# SWEEP.net
KiCad netlist of a schematic drawn in Altium Designer
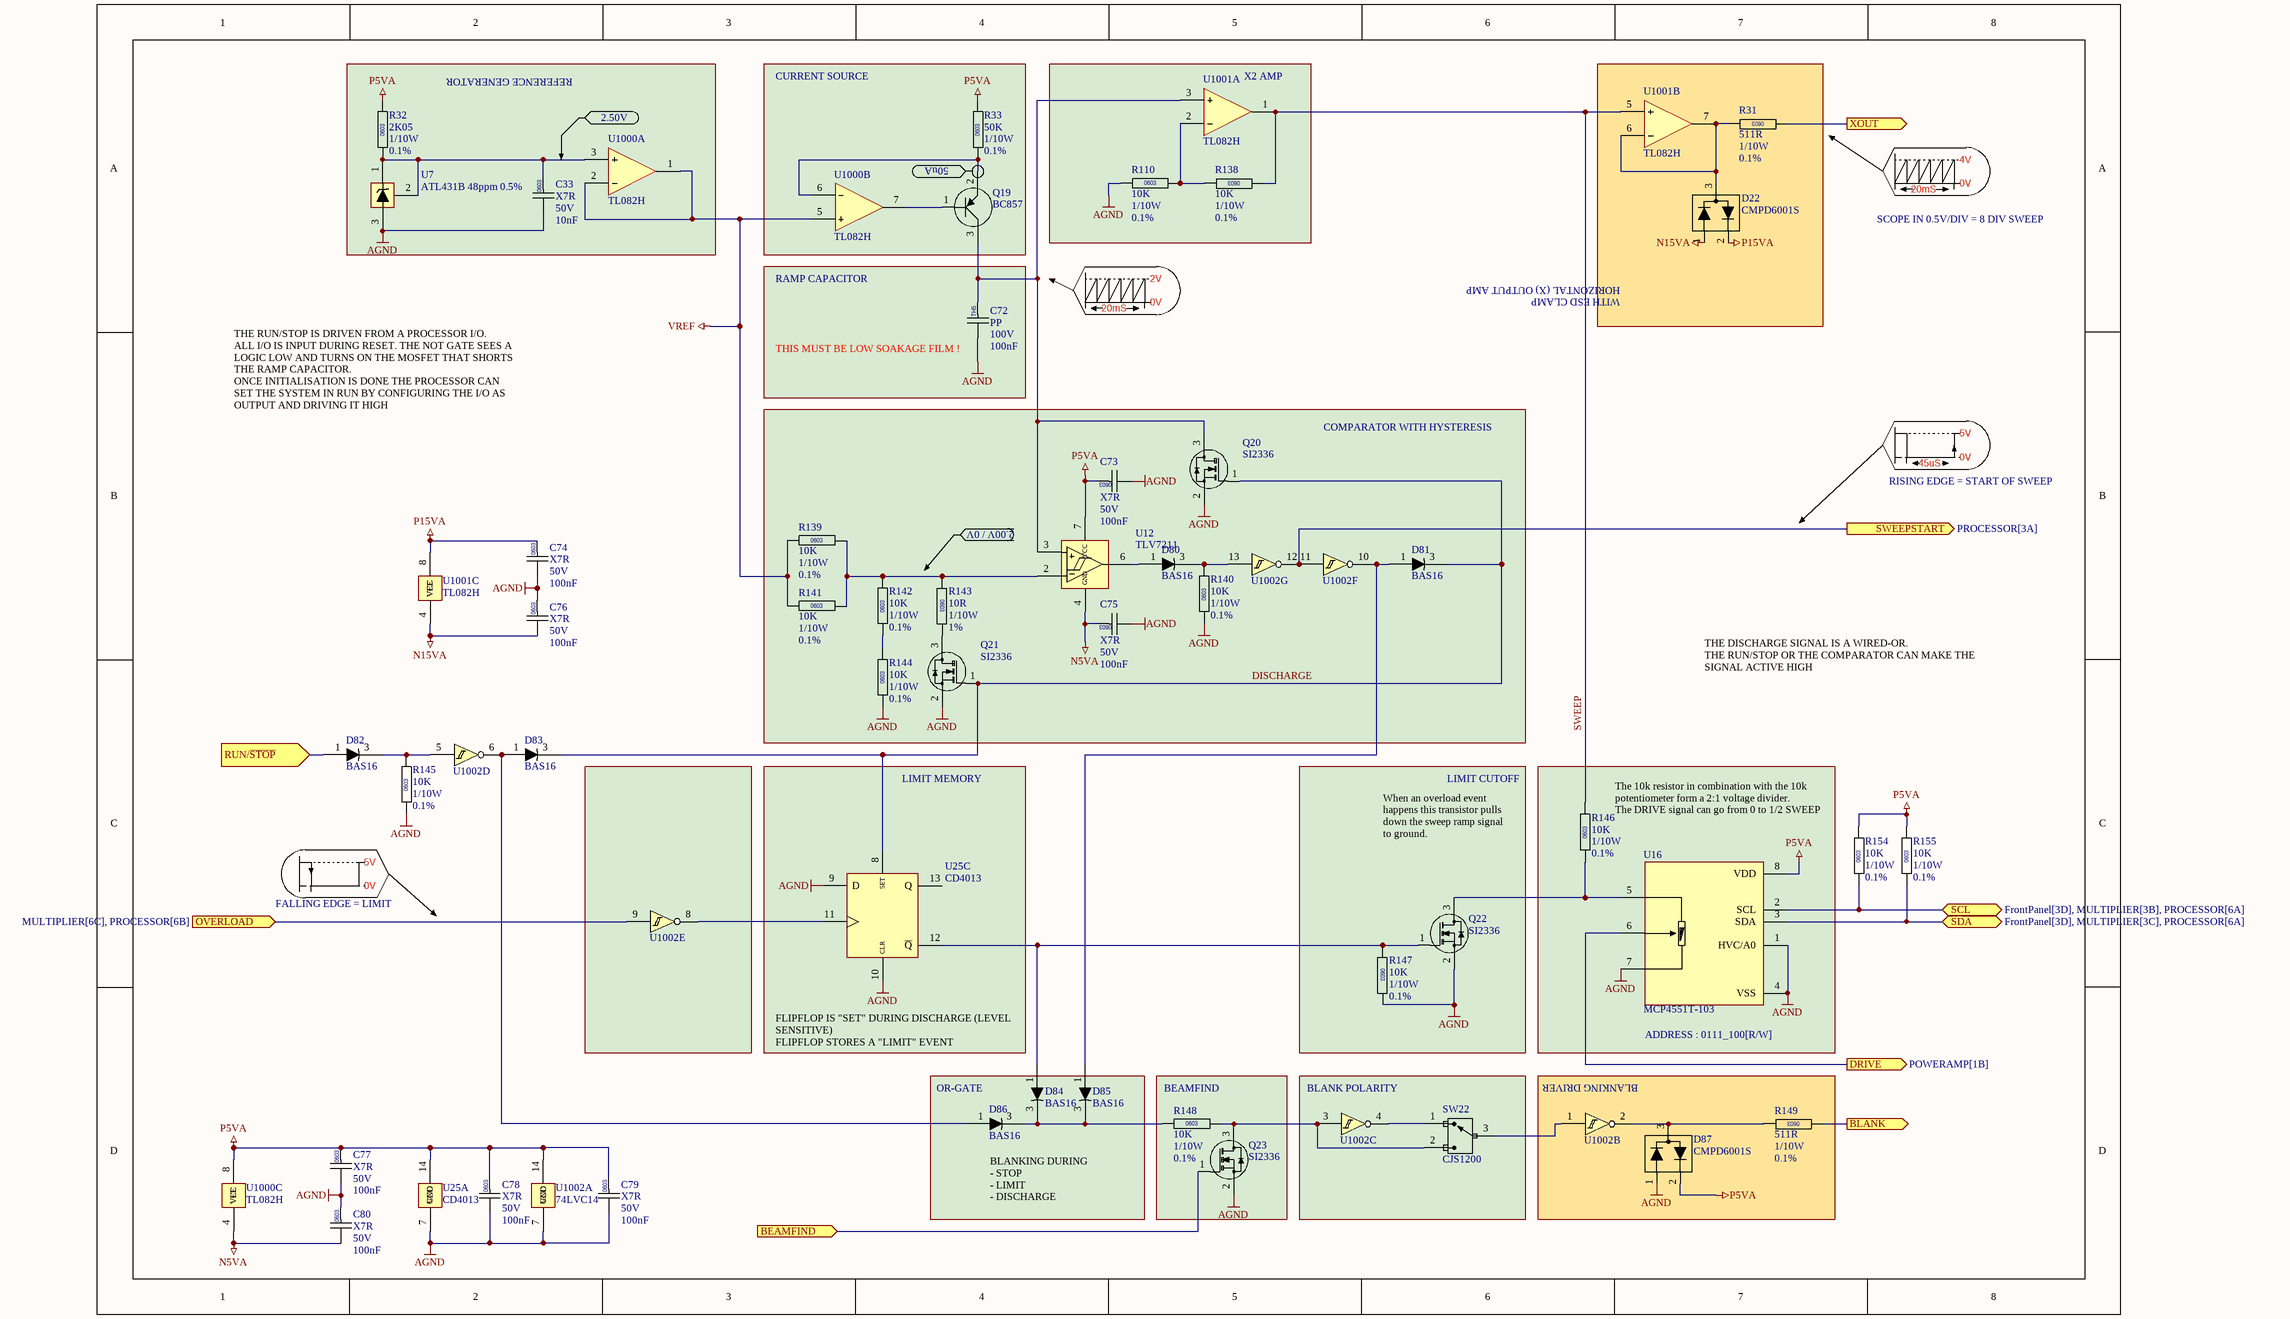
[diagram p0: SWEEP.SchDoc]

(export (version "E")
  (design (tool "Eeschema 10.0.6"))
  (components
    (comp (ref "C33")
      (value "CAP0603")
      (footprint "CAPC0603")
      (description "CAPACITOR,CERAMIC,10nF,50V,X7R,0603")
      (fields
        (field (name "DIELECTRIC") "X7R")
        (field (name "VOLTAGE") "50V")
        (field (name "CAPACITANCE") "10nF")
      )
      (libsource (lib "CAPACITORS") (part "CAPC-0603-10nF-50V-X7R"))
    )
    (comp (ref "C72")
      (value "CAPF")
      (footprint "CAPF50P720X720")
      (description "CAPACITOR,POLYPROP,100nF,100V")
      (fields
        (field (name "DIELECTRIC") "PP")
        (field (name "VOLTAGE") "100V")
        (field (name "CAPACITANCE") "100nF")
      )
      (libsource (lib "CAPACITORS") (part "CAPF-100nF-100V"))
    )
    (comp (ref "C73")
      (value "CAP0603")
      (footprint "CAPC0603")
      (description "CAPACITOR,CERAMIC,100nF,50V,X7R,0603")
      (fields
        (field (name "DIELECTRIC") "X7R")
        (field (name "VOLTAGE") "50V")
        (field (name "CAPACITANCE") "100nF")
      )
      (libsource (lib "CAPACITORS") (part "CAPC-0603-100nF-50V-X7R"))
    )
    (comp (ref "C74")
      (value "CAP0603")
      (footprint "CAPC0603")
      (description "CAPACITOR,CERAMIC,100nF,50V,X7R,0603")
      (fields
        (field (name "DIELECTRIC") "X7R")
        (field (name "VOLTAGE") "50V")
        (field (name "CAPACITANCE") "100nF")
      )
      (libsource (lib "CAPACITORS") (part "CAPC-0603-100nF-50V-X7R"))
    )
    (comp (ref "C75")
      (value "CAP0603")
      (footprint "CAPC0603")
      (description "CAPACITOR,CERAMIC,100nF,50V,X7R,0603")
      (fields
        (field (name "DIELECTRIC") "X7R")
        (field (name "VOLTAGE") "50V")
        (field (name "CAPACITANCE") "100nF")
      )
      (libsource (lib "CAPACITORS") (part "CAPC-0603-100nF-50V-X7R"))
    )
    (comp (ref "C76")
      (value "CAP0603")
      (footprint "CAPC0603")
      (description "CAPACITOR,CERAMIC,100nF,50V,X7R,0603")
      (fields
        (field (name "DIELECTRIC") "X7R")
        (field (name "VOLTAGE") "50V")
        (field (name "CAPACITANCE") "100nF")
      )
      (libsource (lib "CAPACITORS") (part "CAPC-0603-100nF-50V-X7R"))
    )
    (comp (ref "C77")
      (value "CAP0603")
      (footprint "CAPC0603")
      (description "CAPACITOR,CERAMIC,100nF,50V,X7R,0603")
      (fields
        (field (name "DIELECTRIC") "X7R")
        (field (name "VOLTAGE") "50V")
        (field (name "CAPACITANCE") "100nF")
      )
      (libsource (lib "CAPACITORS") (part "CAPC-0603-100nF-50V-X7R"))
    )
    (comp (ref "C78")
      (value "CAP0603")
      (footprint "CAPC0603")
      (description "CAPACITOR,CERAMIC,100nF,50V,X7R,0603")
      (fields
        (field (name "DIELECTRIC") "X7R")
        (field (name "VOLTAGE") "50V")
        (field (name "CAPACITANCE") "100nF")
      )
      (libsource (lib "CAPACITORS") (part "CAPC-0603-100nF-50V-X7R"))
    )
    (comp (ref "C79")
      (value "CAP0603")
      (footprint "CAPC0603")
      (description "CAPACITOR,CERAMIC,100nF,50V,X7R,0603")
      (fields
        (field (name "DIELECTRIC") "X7R")
        (field (name "VOLTAGE") "50V")
        (field (name "CAPACITANCE") "100nF")
      )
      (libsource (lib "CAPACITORS") (part "CAPC-0603-100nF-50V-X7R"))
    )
    (comp (ref "C80")
      (value "CAP0603")
      (footprint "CAPC0603")
      (description "CAPACITOR,CERAMIC,100nF,50V,X7R,0603")
      (fields
        (field (name "DIELECTRIC") "X7R")
        (field (name "VOLTAGE") "50V")
        (field (name "CAPACITANCE") "100nF")
      )
      (libsource (lib "CAPACITORS") (part "CAPC-0603-100nF-50V-X7R"))
    )
    (comp (ref "D22")
      (value "CMPD6001S")
      (footprint "SOT23")
      (description "DIODE,75V,250mA,SOT23,500pA ULTRA LOW LEAKAGE")
      (libsource (lib "DIODES") (part "DIODE-CENTRALSEMI-CMPD6001S"))
    )
    (comp (ref "D80")
      (value "BAS16")
      (footprint "SOT23")
      (description "DIODE,RECTIFIER,75V,0.3A,BAS16,SOT23")
      (libsource (lib "DIODES") (part "DIODE-RECTIFIER-DIODES-BAS16-SOT23"))
    )
    (comp (ref "D81")
      (value "BAS16")
      (footprint "SOT23")
      (description "DIODE,RECTIFIER,75V,0.3A,BAS16,SOT23")
      (libsource (lib "DIODES") (part "DIODE-RECTIFIER-DIODES-BAS16-SOT23"))
    )
    (comp (ref "D82")
      (value "BAS16")
      (footprint "SOT23")
      (description "DIODE,RECTIFIER,75V,0.3A,BAS16,SOT23")
      (libsource (lib "DIODES") (part "DIODE-RECTIFIER-DIODES-BAS16-SOT23"))
    )
    (comp (ref "D83")
      (value "BAS16")
      (footprint "SOT23")
      (description "DIODE,RECTIFIER,75V,0.3A,BAS16,SOT23")
      (libsource (lib "DIODES") (part "DIODE-RECTIFIER-DIODES-BAS16-SOT23"))
    )
    (comp (ref "D84")
      (value "BAS16")
      (footprint "SOT23")
      (description "DIODE,RECTIFIER,75V,0.3A,BAS16,SOT23")
      (libsource (lib "DIODES") (part "DIODE-RECTIFIER-DIODES-BAS16-SOT23"))
    )
    (comp (ref "D85")
      (value "BAS16")
      (footprint "SOT23")
      (description "DIODE,RECTIFIER,75V,0.3A,BAS16,SOT23")
      (libsource (lib "DIODES") (part "DIODE-RECTIFIER-DIODES-BAS16-SOT23"))
    )
    (comp (ref "D86")
      (value "BAS16")
      (footprint "SOT23")
      (description "DIODE,RECTIFIER,75V,0.3A,BAS16,SOT23")
      (libsource (lib "DIODES") (part "DIODE-RECTIFIER-DIODES-BAS16-SOT23"))
    )
    (comp (ref "D87")
      (value "CMPD6001S")
      (footprint "SOT23")
      (description "DIODE,75V,250mA,SOT23,500pA ULTRA LOW LEAKAGE")
      (libsource (lib "DIODES") (part "DIODE-CENTRALSEMI-CMPD6001S"))
    )
    (comp (ref "Q19")
      (value "BC857")
      (footprint "SOT23")
      (description "XSTR,PNP,SOT23,BC857,SOT23")
      (libsource (lib "TRANSISTORS") (part "XSTR-PNP-BC857"))
    )
    (comp (ref "Q20")
      (value "SI2336")
      (footprint "SOT23")
      (description "XSTR,NMOS,30V,4.3A,SI2336DS-T1-BE3.SOT23")
      (libsource (lib "TRANSISTORS") (part "XSTR-NMOS-VISHAY-SI2336DS-T1-BE3"))
    )
    (comp (ref "Q21")
      (value "SI2336")
      (footprint "SOT23")
      (description "XSTR,NMOS,30V,4.3A,SI2336DS-T1-BE3.SOT23")
      (libsource (lib "TRANSISTORS") (part "XSTR-NMOS-VISHAY-SI2336DS-T1-BE3"))
    )
    (comp (ref "Q22")
      (value "SI2336")
      (footprint "SOT23")
      (description "XSTR,NMOS,30V,4.3A,SI2336DS-T1-BE3.SOT23")
      (libsource (lib "TRANSISTORS") (part "XSTR-NMOS-VISHAY-SI2336DS-T1-BE3"))
    )
    (comp (ref "Q23")
      (value "SI2336")
      (footprint "SOT23")
      (description "XSTR,NMOS,30V,4.3A,SI2336DS-T1-BE3.SOT23")
      (libsource (lib "TRANSISTORS") (part "XSTR-NMOS-VISHAY-SI2336DS-T1-BE3"))
    )
    (comp (ref "R31")
      (value "511R")
      (footprint "RESC0603")
      (description "RESISTOR,511R,0.1%,100mW,0603 (1608)")
      (fields
        (field (name "POWER") "1/10W")
        (field (name "TOLERANCE") "0.1%")
        (field (name "Comment") "RESC0603")
      )
      (libsource (lib "RESISTORS") (part "RESC-0603-511R-0.1%"))
    )
    (comp (ref "R32")
      (value "2K05")
      (footprint "RESC0603")
      (description "RESISTOR,2K05,0.11%,100mW,0603 (1608)")
      (fields
        (field (name "POWER") "1/10W")
        (field (name "TOLERANCE") "0.1%")
        (field (name "Comment") "RESC0603")
      )
      (libsource (lib "RESISTORS") (part "RESC-0603-2K05-0.1%-1/10W"))
    )
    (comp (ref "R33")
      (value "50K")
      (footprint "RESC0603")
      (description "RESISTOR,50K,0.1%,100mW,0603 (1608)")
      (fields
        (field (name "POWER") "1/10W")
        (field (name "TOLERANCE") "0.1%")
        (field (name "Comment") "RESC0603")
      )
      (libsource (lib "RESISTORS") (part "RESC-0603-50K-0.1%-1/10W"))
    )
    (comp (ref "R110")
      (value "10K")
      (footprint "RESC0603")
      (description "RESISTOR,10K,0.1%,100mW,0603 (1608)")
      (fields
        (field (name "POWER") "1/10W")
        (field (name "TOLERANCE") "0.1%")
        (field (name "Comment") "RESC0603")
      )
      (libsource (lib "RESISTORS") (part "RESC-0603-10K-0.1%-1/10W"))
    )
    (comp (ref "R138")
      (value "10K")
      (footprint "RESC0603")
      (description "RESISTOR,10K,0.1%,100mW,0603 (1608)")
      (fields
        (field (name "POWER") "1/10W")
        (field (name "TOLERANCE") "0.1%")
        (field (name "Comment") "RESC0603")
      )
      (libsource (lib "RESISTORS") (part "RESC-0603-10K-0.1%-1/10W"))
    )
    (comp (ref "R139")
      (value "10K")
      (footprint "RESC0603")
      (description "RESISTOR,10K,0.1%,100mW,0603 (1608)")
      (fields
        (field (name "POWER") "1/10W")
        (field (name "TOLERANCE") "0.1%")
        (field (name "Comment") "RESC0603")
      )
      (libsource (lib "RESISTORS") (part "RESC-0603-10K-0.1%-1/10W"))
    )
    (comp (ref "R140")
      (value "10K")
      (footprint "RESC0603")
      (description "RESISTOR,10K,0.1%,100mW,0603 (1608)")
      (fields
        (field (name "POWER") "1/10W")
        (field (name "TOLERANCE") "0.1%")
        (field (name "Comment") "RESC0603")
      )
      (libsource (lib "RESISTORS") (part "RESC-0603-10K-0.1%-1/10W"))
    )
    (comp (ref "R141")
      (value "10K")
      (footprint "RESC0603")
      (description "RESISTOR,10K,0.1%,100mW,0603 (1608)")
      (fields
        (field (name "POWER") "1/10W")
        (field (name "TOLERANCE") "0.1%")
        (field (name "Comment") "RESC0603")
      )
      (libsource (lib "RESISTORS") (part "RESC-0603-10K-0.1%-1/10W"))
    )
    (comp (ref "R142")
      (value "10K")
      (footprint "RESC0603")
      (description "RESISTOR,10K,0.1%,100mW,0603 (1608)")
      (fields
        (field (name "POWER") "1/10W")
        (field (name "TOLERANCE") "0.1%")
        (field (name "Comment") "RESC0603")
      )
      (libsource (lib "RESISTORS") (part "RESC-0603-10K-0.1%-1/10W"))
    )
    (comp (ref "R143")
      (value "10R")
      (footprint "RESC0603")
      (description "RESISTOR,10R,1%,100mW,0603 (1608)")
      (fields
        (field (name "POWER") "1/10W")
        (field (name "TOLERANCE") "1%")
        (field (name "Comment") "RESC0603")
      )
      (libsource (lib "RESISTORS") (part "RESC-0603-10R-1%-1/10W"))
    )
    (comp (ref "R144")
      (value "10K")
      (footprint "RESC0603")
      (description "RESISTOR,10K,0.1%,100mW,0603 (1608)")
      (fields
        (field (name "POWER") "1/10W")
        (field (name "TOLERANCE") "0.1%")
        (field (name "Comment") "RESC0603")
      )
      (libsource (lib "RESISTORS") (part "RESC-0603-10K-0.1%-1/10W"))
    )
    (comp (ref "R145")
      (value "10K")
      (footprint "RESC0603")
      (description "RESISTOR,10K,0.1%,100mW,0603 (1608)")
      (fields
        (field (name "POWER") "1/10W")
        (field (name "TOLERANCE") "0.1%")
        (field (name "Comment") "RESC0603")
      )
      (libsource (lib "RESISTORS") (part "RESC-0603-10K-0.1%-1/10W"))
    )
    (comp (ref "R146")
      (value "10K")
      (footprint "RESC0603")
      (description "RESISTOR,10K,0.1%,100mW,0603 (1608)")
      (fields
        (field (name "POWER") "1/10W")
        (field (name "TOLERANCE") "0.1%")
        (field (name "Comment") "RESC0603")
      )
      (libsource (lib "RESISTORS") (part "RESC-0603-10K-0.1%-1/10W"))
    )
    (comp (ref "R147")
      (value "10K")
      (footprint "RESC0603")
      (description "RESISTOR,10K,0.1%,100mW,0603 (1608)")
      (fields
        (field (name "POWER") "1/10W")
        (field (name "TOLERANCE") "0.1%")
        (field (name "Comment") "RESC0603")
      )
      (libsource (lib "RESISTORS") (part "RESC-0603-10K-0.1%-1/10W"))
    )
    (comp (ref "R148")
      (value "10K")
      (footprint "RESC0603")
      (description "RESISTOR,10K,0.1%,100mW,0603 (1608)")
      (fields
        (field (name "POWER") "1/10W")
        (field (name "TOLERANCE") "0.1%")
        (field (name "Comment") "RESC0603")
      )
      (libsource (lib "RESISTORS") (part "RESC-0603-10K-0.1%-1/10W"))
    )
    (comp (ref "R149")
      (value "511R")
      (footprint "RESC0603")
      (description "RESISTOR,511R,0.1%,100mW,0603 (1608)")
      (fields
        (field (name "POWER") "1/10W")
        (field (name "TOLERANCE") "0.1%")
        (field (name "Comment") "RESC0603")
      )
      (libsource (lib "RESISTORS") (part "RESC-0603-511R-0.1%"))
    )
    (comp (ref "R154")
      (value "10K")
      (footprint "RESC0603")
      (description "RESISTOR,10K,0.1%,100mW,0603 (1608)")
      (fields
        (field (name "POWER") "1/10W")
        (field (name "TOLERANCE") "0.1%")
        (field (name "Comment") "RESC0603")
      )
      (libsource (lib "RESISTORS") (part "RESC-0603-10K-0.1%-1/10W"))
    )
    (comp (ref "R155")
      (value "10K")
      (footprint "RESC0603")
      (description "RESISTOR,10K,0.1%,100mW,0603 (1608)")
      (fields
        (field (name "POWER") "1/10W")
        (field (name "TOLERANCE") "0.1%")
        (field (name "Comment") "RESC0603")
      )
      (libsource (lib "RESISTORS") (part "RESC-0603-10K-0.1%-1/10W"))
    )
    (comp (ref "SW22")
      (value "CJS1200")
      (footprint "SWITCH-NIDEC-CJS-1200TB1")
      (description "SWITCH,SPST,SLIDE,SMD")
      (libsource (lib "SWITCH") (part "SWITCH-NIDEC-CJS-1200TB1"))
    )
    (comp (ref "U7")
      (value "ATL431B 48ppm 0.5%")
      (footprint "SOT23")
      (description "IC,REGULATOR,REFERENCE,SHUNT,0.5%,48ppm,TL431,SOT23")
      (libsource (lib "IC-ANALOG") (part "IC-TI-ATL431B-SOT23"))
    )
    (comp (ref "U12")
      (value "TLV7211")
      (footprint "SO127P600-8N")
      (description "IC,COMPARATOR,SINGLE,PUSHPULL,TI,TLV7211,SO8")
      (libsource (lib "IC-OPAMP") (part "IC-TI-TLV7211-SO8"))
    )
    (comp (ref "U16")
      (value "MCP4551T-103")
      (footprint "SO65P490-8N")
      (description "IC,DIGITAL POTMETER,257STEP,I2C,10K,MICROCHIP,MCP4551T-103")
      (libsource (lib "IC-I2C") (part "IC-MICROCHIP-MCP4551T-103"))
    )
    (comp (ref "U25")
      (value "CD4013")
      (footprint "SO127P600-14N")
      (description "IC,LOGIC,CMOS,4XXX,DUAL D-FLIPFLOP,CD4013")
      (libsource (lib "IC-4XXX") (part "IC-TI-CD4013-SO14"))
    )
    (comp (ref "U1000")
      (value "TL082H")
      (footprint "SO127P600-8N")
      (description "IC,OPAMP JFET,DUAL,TL082HIDR,SO8")
      (libsource (lib "IC-OPAMP") (part "IC-TI-TL082H-SO8"))
    )
    (comp (ref "U1001")
      (value "TL082H")
      (footprint "SO127P600-8N")
      (description "IC,OPAMP JFET,DUAL,TL082HIDR,SO8")
      (libsource (lib "") (part "IC-TI-TL082H-SO8_1"))
    )
    (comp (ref "U1002")
      (value "74LVC14")
      (footprint "SO127P600-14N")
      (description "IC,LOGIC,CMOS,74XX,HEX SCHMITTTRIGGER,74LVC14AS14-13,SO14")
      (libsource (lib "IC-74XX") (part "IC-DIODES-74LVC14AS14-13-SO14"))
    )
  )
  (nets
    (net (code "1") (name "/BEAMFIND") (class "Default")
      (node (ref "Q23") (pin "1") (pinfunction "G1_1") (pintype "passive"))
    )
    (net (code "2") (name "/BLANK") (class "Default") (node (ref "R149") (pin "2") (pintype "passive")))
    (net (code "3") (name "/DISCHARGE") (class "Default")
      (node (ref "D81") (pin "3") (pinfunction "K_3") (pintype "passive"))
      (node (ref "D83") (pin "3") (pinfunction "K_3") (pintype "passive"))
      (node (ref "Q20") (pin "1") (pinfunction "G1_1") (pintype "passive"))
      (node (ref "Q21") (pin "1") (pinfunction "G1_1") (pintype "passive"))
      (node (ref "U25") (pin "8") (pinfunction "SET_8") (pintype "passive"))
    )
    (net (code "4") (name "/DRIVE") (class "Default")
      (node (ref "U16") (pin "6") (pinfunction "OW_6") (pintype "passive"))
    )
    (net (code "5") (name "/OVERLOAD") (class "Default")
      (node (ref "U1002") (pin "9") (pinfunction "9_9") (pintype "passive"))
    )
    (net (code "6") (name "/RUN{slash}~{STOP}") (class "Default")
      (node (ref "D82") (pin "1") (pinfunction "A_1") (pintype "passive"))
    )
    (net (code "7") (name "/SCL") (class "Default")
      (node (ref "R154") (pin "2") (pintype "passive"))
      (node (ref "U16") (pin "2") (pinfunction "SCL_2") (pintype "passive"))
    )
    (net (code "8") (name "/SDA") (class "Default")
      (node (ref "R155") (pin "2") (pintype "passive"))
      (node (ref "U16") (pin "3") (pinfunction "SDA_3") (pintype "passive"))
    )
    (net (code "9") (name "/SWEEP") (class "Default")
      (node (ref "R138") (pin "2") (pintype "passive"))
      (node (ref "R146") (pin "1") (pintype "passive"))
      (node (ref "U1001") (pin "1") (pinfunction "O_1") (pintype "passive"))
      (node (ref "U1001") (pin "5") (pinfunction "+_5") (pintype "passive"))
    )
    (net (code "10") (name "/SWEEPSTART") (class "Default")
      (node (ref "U1002") (pin "11") (pinfunction "11_11") (pintype "passive"))
      (node (ref "U1002") (pin "12") (pinfunction "12_12") (pintype "passive"))
    )
    (net (code "11") (name "/XOUT") (class "Default") (node (ref "R31") (pin "2") (pintype "passive")))
    (net (code "12") (name "AGND") (class "Default")
      (node (ref "C33") (pin "2") (pintype "passive"))
      (node (ref "C72") (pin "2") (pintype "passive"))
      (node (ref "C73") (pin "2") (pintype "passive"))
      (node (ref "C74") (pin "2") (pintype "passive"))
      (node (ref "C75") (pin "2") (pintype "passive"))
      (node (ref "C76") (pin "1") (pintype "passive"))
      (node (ref "C77") (pin "2") (pintype "passive"))
      (node (ref "C78") (pin "2") (pintype "passive"))
      (node (ref "C79") (pin "2") (pintype "passive"))
      (node (ref "C80") (pin "1") (pintype "passive"))
      (node (ref "D87") (pin "1") (pinfunction "K_1") (pintype "passive"))
      (node (ref "Q20") (pin "2") (pinfunction "S_2") (pintype "passive"))
      (node (ref "Q21") (pin "2") (pinfunction "S_2") (pintype "passive"))
      (node (ref "Q22") (pin "2") (pinfunction "S_2") (pintype "passive"))
      (node (ref "Q23") (pin "2") (pinfunction "S_2") (pintype "passive"))
      (node (ref "R110") (pin "2") (pintype "passive"))
      (node (ref "R140") (pin "2") (pintype "passive"))
      (node (ref "R144") (pin "2") (pintype "passive"))
      (node (ref "R145") (pin "2") (pintype "passive"))
      (node (ref "R147") (pin "1") (pintype "passive"))
      (node (ref "U1002") (pin "7") (pinfunction "GND_7") (pintype "passive"))
      (node (ref "U16") (pin "1") (pinfunction "HVC/A0_1") (pintype "passive"))
      (node (ref "U16") (pin "4") (pinfunction "VSS_4") (pintype "passive"))
      (node (ref "U16") (pin "7") (pinfunction "POB_7") (pintype "passive"))
      (node (ref "U25") (pin "10") (pinfunction "CLR_10") (pintype "passive"))
      (node (ref "U25") (pin "7") (pinfunction "GND_7") (pintype "passive"))
      (node (ref "U25") (pin "9") (pinfunction "D_9") (pintype "passive"))
      (node (ref "U7") (pin "3") (pinfunction "3_3") (pintype "passive"))
    )
    (net (code "13") (name "N5VA") (class "Default")
      (node (ref "C75") (pin "1") (pintype "passive"))
      (node (ref "C80") (pin "2") (pintype "passive"))
      (node (ref "U1000") (pin "4") (pinfunction "VEE_4") (pintype "passive"))
      (node (ref "U12") (pin "4") (pinfunction "GND_4") (pintype "passive"))
    )
    (net (code "14") (name "N15VA") (class "Default")
      (node (ref "C76") (pin "2") (pintype "passive"))
      (node (ref "D22") (pin "1") (pinfunction "K_1") (pintype "passive"))
      (node (ref "U1001") (pin "4") (pinfunction "VEE_4") (pintype "passive"))
    )
    (net (code "15") (name "Net-(D80-A)") (class "Default")
      (node (ref "D80") (pin "1") (pinfunction "A_1") (pintype "passive"))
      (node (ref "U12") (pin "6") (pinfunction "OUT_6") (pintype "passive"))
    )
    (net (code "16") (name "Net-(D80-K)") (class "Default")
      (node (ref "D80") (pin "3") (pinfunction "K_3") (pintype "passive"))
      (node (ref "R140") (pin "1") (pintype "passive"))
      (node (ref "U1002") (pin "13") (pinfunction "13_13") (pintype "passive"))
    )
    (net (code "17") (name "Net-(D81-A)") (class "Default")
      (node (ref "D81") (pin "1") (pinfunction "A_1") (pintype "passive"))
      (node (ref "D85") (pin "1") (pinfunction "A_1") (pintype "passive"))
      (node (ref "U1002") (pin "10") (pinfunction "10_10") (pintype "passive"))
    )
    (net (code "18") (name "Net-(D82-K)") (class "Default")
      (node (ref "D82") (pin "3") (pinfunction "K_3") (pintype "passive"))
      (node (ref "R145") (pin "1") (pintype "passive"))
      (node (ref "U1002") (pin "5") (pinfunction "5_5") (pintype "passive"))
    )
    (net (code "19") (name "Net-(D83-A)") (class "Default")
      (node (ref "D83") (pin "1") (pinfunction "A_1") (pintype "passive"))
      (node (ref "D86") (pin "1") (pinfunction "A_1") (pintype "passive"))
      (node (ref "U1002") (pin "6") (pinfunction "6_6") (pintype "passive"))
    )
    (net (code "20") (name "Net-(D84-A)") (class "Default")
      (node (ref "D84") (pin "1") (pinfunction "A_1") (pintype "passive"))
      (node (ref "Q22") (pin "1") (pinfunction "G1_1") (pintype "passive"))
      (node (ref "R147") (pin "2") (pintype "passive"))
      (node (ref "U25") (pin "12") (pinfunction "~{Q}_12") (pintype "passive"))
    )
    (net (code "21") (name "Net-(D84-K)") (class "Default")
      (node (ref "D84") (pin "3") (pinfunction "K_3") (pintype "passive"))
      (node (ref "D85") (pin "3") (pinfunction "K_3") (pintype "passive"))
      (node (ref "D86") (pin "3") (pinfunction "K_3") (pintype "passive"))
      (node (ref "R148") (pin "2") (pintype "passive"))
    )
    (net (code "22") (name "Net-(D87-A-Pad3)") (class "Default")
      (node (ref "D87") (pin "3") (pinfunction "A_3") (pintype "passive"))
      (node (ref "R149") (pin "1") (pintype "passive"))
      (node (ref "U1002") (pin "2") (pinfunction "2_2") (pintype "passive"))
    )
    (net (code "23") (name "Net-(Q19-B)") (class "Default")
      (node (ref "Q19") (pin "1") (pinfunction "B_1") (pintype "passive"))
      (node (ref "U1000") (pin "7") (pinfunction "O_7") (pintype "passive"))
    )
    (net (code "24") (name "Net-(Q19-C)") (class "Default")
      (node (ref "C72") (pin "1") (pintype "passive"))
      (node (ref "Q19") (pin "3") (pinfunction "C_3") (pintype "passive"))
      (node (ref "Q20") (pin "3") (pinfunction "D_3") (pintype "passive"))
      (node (ref "U1001") (pin "3") (pinfunction "+_3") (pintype "passive"))
      (node (ref "U12") (pin "3") (pinfunction "+_3") (pintype "passive"))
    )
    (net (code "25") (name "Net-(Q19-E)") (class "Default")
      (node (ref "Q19") (pin "2") (pinfunction "E_2") (pintype "passive"))
      (node (ref "R33") (pin "2") (pintype "passive"))
      (node (ref "U1000") (pin "6") (pinfunction "-_6") (pintype "passive"))
    )
    (net (code "26") (name "Net-(Q21-D)") (class "Default")
      (node (ref "Q21") (pin "3") (pinfunction "D_3") (pintype "passive"))
      (node (ref "R143") (pin "1") (pintype "passive"))
    )
    (net (code "27") (name "Net-(Q22-D)") (class "Default")
      (node (ref "Q22") (pin "3") (pinfunction "D_3") (pintype "passive"))
      (node (ref "R146") (pin "2") (pintype "passive"))
      (node (ref "U16") (pin "5") (pinfunction "POA_5") (pintype "passive"))
    )
    (net (code "28") (name "Net-(Q23-D)") (class "Default")
      (node (ref "Q23") (pin "3") (pinfunction "D_3") (pintype "passive"))
      (node (ref "R148") (pin "1") (pintype "passive"))
      (node (ref "SW22") (pin "2") (pinfunction "2_2") (pintype "passive"))
      (node (ref "U1002") (pin "3") (pinfunction "3_3") (pintype "passive"))
    )
    (net (code "29") (name "Net-(R142-Pad2)") (class "Default")
      (node (ref "R142") (pin "2") (pintype "passive"))
      (node (ref "R144") (pin "1") (pintype "passive"))
    )
    (net (code "30") (name "Net-(SW22-Pad1)") (class "Default")
      (node (ref "SW22") (pin "1") (pinfunction "1_1") (pintype "passive"))
      (node (ref "U1002") (pin "4") (pinfunction "4_4") (pintype "passive"))
    )
    (net (code "31") (name "Net-(SW22-Pad3)") (class "Default")
      (node (ref "SW22") (pin "3") (pinfunction "3_3") (pintype "passive"))
      (node (ref "U1002") (pin "1") (pinfunction "1_1") (pintype "passive"))
    )
    (net (code "32") (name "Net-(U12--)") (class "Default")
      (node (ref "R139") (pin "1") (pintype "passive"))
      (node (ref "R141") (pin "1") (pintype "passive"))
      (node (ref "R142") (pin "1") (pintype "passive"))
      (node (ref "R143") (pin "2") (pintype "passive"))
      (node (ref "U12") (pin "2") (pinfunction "-_2") (pintype "passive"))
    )
    (net (code "33") (name "Net-(U25C-CLK)") (class "Default")
      (node (ref "U1002") (pin "8") (pinfunction "8_8") (pintype "passive"))
      (node (ref "U25") (pin "11") (pinfunction "CLK_11") (pintype "passive"))
    )
    (net (code "34") (name "Net-(U1000A-+)") (class "Default")
      (node (ref "C33") (pin "1") (pintype "passive"))
      (node (ref "R32") (pin "2") (pintype "passive"))
      (node (ref "U1000") (pin "3") (pinfunction "+_3") (pintype "passive"))
      (node (ref "U7") (pin "1") (pinfunction "1_1") (pintype "passive"))
      (node (ref "U7") (pin "2") (pinfunction "2_2") (pintype "passive"))
    )
    (net (code "35") (name "Net-(U1001A--)") (class "Default")
      (node (ref "R110") (pin "1") (pintype "passive"))
      (node (ref "R138") (pin "1") (pintype "passive"))
      (node (ref "U1001") (pin "2") (pinfunction "-_2") (pintype "passive"))
    )
    (net (code "36") (name "Net-(U1001B--)") (class "Default")
      (node (ref "D22") (pin "3") (pinfunction "A_3") (pintype "passive"))
      (node (ref "R31") (pin "1") (pintype "passive"))
      (node (ref "U1001") (pin "6") (pinfunction "-_6") (pintype "passive"))
      (node (ref "U1001") (pin "7") (pinfunction "O_7") (pintype "passive"))
    )
    (net (code "37") (name "P5VA") (class "Default")
      (node (ref "C73") (pin "1") (pintype "passive"))
      (node (ref "C77") (pin "1") (pintype "passive"))
      (node (ref "C78") (pin "1") (pintype "passive"))
      (node (ref "C79") (pin "1") (pintype "passive"))
      (node (ref "D87") (pin "2") (pinfunction "A_2") (pintype "passive"))
      (node (ref "R154") (pin "1") (pintype "passive"))
      (node (ref "R155") (pin "1") (pintype "passive"))
      (node (ref "R32") (pin "1") (pintype "passive"))
      (node (ref "R33") (pin "1") (pintype "passive"))
      (node (ref "U1000") (pin "8") (pinfunction "VCC_8") (pintype "passive"))
      (node (ref "U1002") (pin "14") (pinfunction "VCC_14") (pintype "passive"))
      (node (ref "U12") (pin "7") (pinfunction "VCC_7") (pintype "passive"))
      (node (ref "U16") (pin "8") (pinfunction "VDD_8") (pintype "passive"))
      (node (ref "U25") (pin "14") (pinfunction "VCC_14") (pintype "passive"))
    )
    (net (code "38") (name "P15VA") (class "Default")
      (node (ref "C74") (pin "1") (pintype "passive"))
      (node (ref "D22") (pin "2") (pinfunction "A_2") (pintype "passive"))
      (node (ref "U1001") (pin "8") (pinfunction "VCC_8") (pintype "passive"))
    )
    (net (code "39") (name "VREF") (class "Default")
      (node (ref "R139") (pin "2") (pintype "passive"))
      (node (ref "R141") (pin "2") (pintype "passive"))
      (node (ref "U1000") (pin "1") (pinfunction "O_1") (pintype "passive"))
      (node (ref "U1000") (pin "2") (pinfunction "-_2") (pintype "passive"))
      (node (ref "U1000") (pin "5") (pinfunction "+_5") (pintype "passive"))
    )
    (net (code "40") (name "unconnected-(U25C-Q-Pad13)") (class "Default")
      (node (ref "U25") (pin "13") (pinfunction "Q_13") (pintype "passive"))
    )
  )
)
